# interface.net
KiCad netlist of a schematic drawn in EAGLE
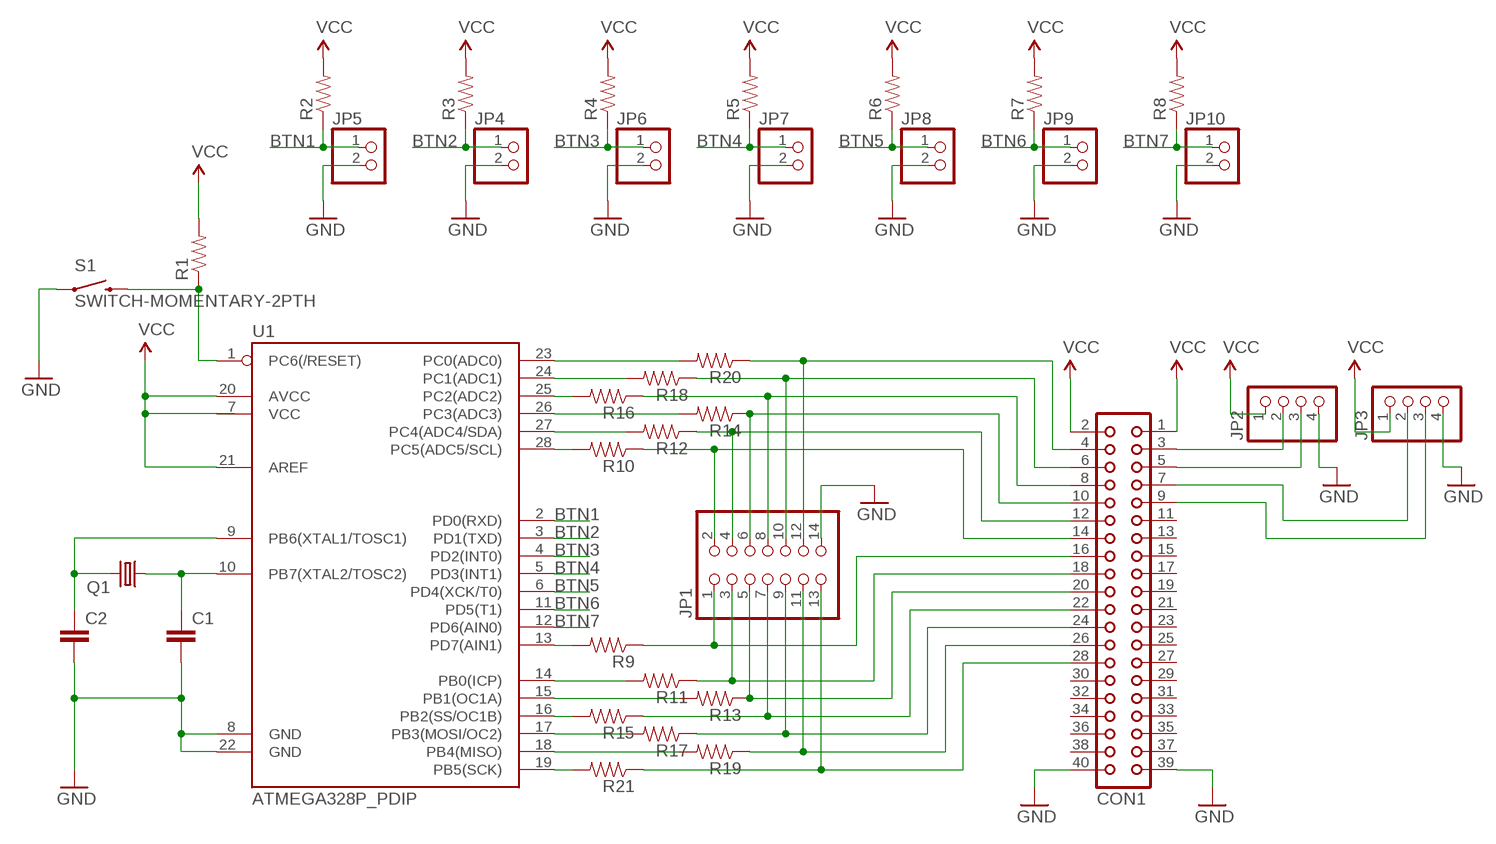
[diagram p0: schematic, sheet 1]

(export (version "E")
  (design (tool "Eeschema 10.0.6"))
  (components
    (comp (ref "C1")
      (value "CAPPTH")
      (footprint "eagle-import:CAP-PTH-SMALL")
      (libsource (lib "eagle-import") (part "CAPPTH"))
    )
    (comp (ref "C2")
      (value "CAPPTH")
      (footprint "eagle-import:CAP-PTH-SMALL")
      (libsource (lib "eagle-import") (part "CAPPTH"))
    )
    (comp (ref "CON1")
      (value "CON40")
      (footprint "eagle-import:CON40")
      (libsource (lib "eagle-import") (part "CON40"))
    )
    (comp (ref "JP1")
      (value "PINHD-2X7")
      (footprint "eagle-import:2X07")
      (libsource (lib "eagle-import") (part "PINHD-2X7"))
    )
    (comp (ref "JP2")
      (value "PINHD-1X4")
      (footprint "eagle-import:1X04")
      (libsource (lib "eagle-import") (part "PINHD-1X4"))
    )
    (comp (ref "JP3")
      (value "PINHD-1X4")
      (footprint "eagle-import:1X04")
      (libsource (lib "eagle-import") (part "PINHD-1X4"))
    )
    (comp (ref "JP4")
      (value "PINHD-1X2")
      (footprint "eagle-import:1X02")
      (libsource (lib "eagle-import") (part "PINHD-1X2"))
    )
    (comp (ref "JP5")
      (value "PINHD-1X2")
      (footprint "eagle-import:1X02")
      (libsource (lib "eagle-import") (part "PINHD-1X2"))
    )
    (comp (ref "JP6")
      (value "PINHD-1X2")
      (footprint "eagle-import:1X02")
      (libsource (lib "eagle-import") (part "PINHD-1X2"))
    )
    (comp (ref "JP7")
      (value "PINHD-1X2")
      (footprint "eagle-import:1X02")
      (libsource (lib "eagle-import") (part "PINHD-1X2"))
    )
    (comp (ref "JP8")
      (value "PINHD-1X2")
      (footprint "eagle-import:1X02")
      (libsource (lib "eagle-import") (part "PINHD-1X2"))
    )
    (comp (ref "JP9")
      (value "PINHD-1X2")
      (footprint "eagle-import:1X02")
      (libsource (lib "eagle-import") (part "PINHD-1X2"))
    )
    (comp (ref "JP10")
      (value "PINHD-1X2")
      (footprint "eagle-import:1X02")
      (libsource (lib "eagle-import") (part "PINHD-1X2"))
    )
    (comp (ref "Q1")
      (value "CRYSTALHC49S")
      (footprint "eagle-import:HC49_S")
      (libsource (lib "eagle-import") (part "CRYSTALHC49S"))
    )
    (comp (ref "R1")
      (value "RESISTORPTH-1/4W")
      (footprint "eagle-import:AXIAL-0.4")
      (libsource (lib "eagle-import") (part "RESISTORPTH-1/4W"))
    )
    (comp (ref "R2")
      (value "RESISTORPTH-1/4W")
      (footprint "eagle-import:AXIAL-0.4")
      (libsource (lib "eagle-import") (part "RESISTORPTH-1/4W"))
    )
    (comp (ref "R3")
      (value "RESISTORPTH-1/4W")
      (footprint "eagle-import:AXIAL-0.4")
      (libsource (lib "eagle-import") (part "RESISTORPTH-1/4W"))
    )
    (comp (ref "R4")
      (value "RESISTORPTH-1/4W")
      (footprint "eagle-import:AXIAL-0.4")
      (libsource (lib "eagle-import") (part "RESISTORPTH-1/4W"))
    )
    (comp (ref "R5")
      (value "RESISTORPTH-1/4W")
      (footprint "eagle-import:AXIAL-0.4")
      (libsource (lib "eagle-import") (part "RESISTORPTH-1/4W"))
    )
    (comp (ref "R6")
      (value "RESISTORPTH-1/4W")
      (footprint "eagle-import:AXIAL-0.4")
      (libsource (lib "eagle-import") (part "RESISTORPTH-1/4W"))
    )
    (comp (ref "R7")
      (value "RESISTORPTH-1/4W")
      (footprint "eagle-import:AXIAL-0.4")
      (libsource (lib "eagle-import") (part "RESISTORPTH-1/4W"))
    )
    (comp (ref "R8")
      (value "RESISTORPTH-1/4W")
      (footprint "eagle-import:AXIAL-0.4")
      (libsource (lib "eagle-import") (part "RESISTORPTH-1/4W"))
    )
    (comp (ref "R9")
      (value "RESISTORPTH-1/4W")
      (footprint "eagle-import:AXIAL-0.4")
      (libsource (lib "eagle-import") (part "RESISTORPTH-1/4W"))
    )
    (comp (ref "R10")
      (value "RESISTORPTH-1/4W")
      (footprint "eagle-import:AXIAL-0.4")
      (libsource (lib "eagle-import") (part "RESISTORPTH-1/4W"))
    )
    (comp (ref "R11")
      (value "RESISTORPTH-1/4W")
      (footprint "eagle-import:AXIAL-0.4")
      (libsource (lib "eagle-import") (part "RESISTORPTH-1/4W"))
    )
    (comp (ref "R12")
      (value "RESISTORPTH-1/4W")
      (footprint "eagle-import:AXIAL-0.4")
      (libsource (lib "eagle-import") (part "RESISTORPTH-1/4W"))
    )
    (comp (ref "R13")
      (value "RESISTORPTH-1/4W")
      (footprint "eagle-import:AXIAL-0.4")
      (libsource (lib "eagle-import") (part "RESISTORPTH-1/4W"))
    )
    (comp (ref "R14")
      (value "RESISTORPTH-1/4W")
      (footprint "eagle-import:AXIAL-0.4")
      (libsource (lib "eagle-import") (part "RESISTORPTH-1/4W"))
    )
    (comp (ref "R15")
      (value "RESISTORPTH-1/4W")
      (footprint "eagle-import:AXIAL-0.4")
      (libsource (lib "eagle-import") (part "RESISTORPTH-1/4W"))
    )
    (comp (ref "R16")
      (value "RESISTORPTH-1/4W")
      (footprint "eagle-import:AXIAL-0.4")
      (libsource (lib "eagle-import") (part "RESISTORPTH-1/4W"))
    )
    (comp (ref "R17")
      (value "RESISTORPTH-1/4W")
      (footprint "eagle-import:AXIAL-0.4")
      (libsource (lib "eagle-import") (part "RESISTORPTH-1/4W"))
    )
    (comp (ref "R18")
      (value "RESISTORPTH-1/4W")
      (footprint "eagle-import:AXIAL-0.4")
      (libsource (lib "eagle-import") (part "RESISTORPTH-1/4W"))
    )
    (comp (ref "R19")
      (value "RESISTORPTH-1/4W")
      (footprint "eagle-import:AXIAL-0.4")
      (libsource (lib "eagle-import") (part "RESISTORPTH-1/4W"))
    )
    (comp (ref "R20")
      (value "RESISTORPTH-1/4W")
      (footprint "eagle-import:AXIAL-0.4")
      (libsource (lib "eagle-import") (part "RESISTORPTH-1/4W"))
    )
    (comp (ref "R21")
      (value "RESISTORPTH-1/4W")
      (footprint "eagle-import:AXIAL-0.4")
      (libsource (lib "eagle-import") (part "RESISTORPTH-1/4W"))
    )
    (comp (ref "S1")
      (value "SWITCH-MOMENTARY-2PTH")
      (footprint "eagle-import:TACTILE-PTH")
      (libsource (lib "eagle-import") (part "SWITCH-MOMENTARY-2PTH"))
    )
    (comp (ref "U1")
      (value "ATMEGA328P_PDIP")
      (footprint "eagle-import:DIL28-3")
      (libsource (lib "eagle-import") (part "ATMEGA328P_PDIP"))
    )
  )
  (nets
    (net (code "1") (name "/BTN1") (class "Default")
      (node (ref "JP5") (pin "1") (pinfunction "1_1") (pintype "passive"))
      (node (ref "R2") (pin "P$1") (pinfunction "1_P$1") (pintype "passive"))
      (node (ref "U1") (pin "2") (pinfunction "PD0(RXD)_2") (pintype "bidirectional"))
    )
    (net (code "2") (name "/BTN2") (class "Default")
      (node (ref "JP4") (pin "1") (pinfunction "1_1") (pintype "passive"))
      (node (ref "R3") (pin "P$1") (pinfunction "1_P$1") (pintype "passive"))
      (node (ref "U1") (pin "3") (pinfunction "PD1(TXD)_3") (pintype "bidirectional"))
    )
    (net (code "3") (name "/BTN3") (class "Default")
      (node (ref "JP6") (pin "1") (pinfunction "1_1") (pintype "passive"))
      (node (ref "R4") (pin "P$1") (pinfunction "1_P$1") (pintype "passive"))
      (node (ref "U1") (pin "4") (pinfunction "PD2(INT0)_4") (pintype "bidirectional"))
    )
    (net (code "4") (name "/BTN4") (class "Default")
      (node (ref "JP7") (pin "1") (pinfunction "1_1") (pintype "passive"))
      (node (ref "R5") (pin "P$1") (pinfunction "1_P$1") (pintype "passive"))
      (node (ref "U1") (pin "5") (pinfunction "PD3(INT1)_5") (pintype "bidirectional"))
    )
    (net (code "5") (name "/BTN5") (class "Default")
      (node (ref "JP8") (pin "1") (pinfunction "1_1") (pintype "passive"))
      (node (ref "R6") (pin "P$1") (pinfunction "1_P$1") (pintype "passive"))
      (node (ref "U1") (pin "6") (pinfunction "PD4(XCK/T0)_6") (pintype "bidirectional"))
    )
    (net (code "6") (name "/BTN6") (class "Default")
      (node (ref "JP9") (pin "1") (pinfunction "1_1") (pintype "passive"))
      (node (ref "R7") (pin "P$1") (pinfunction "1_P$1") (pintype "passive"))
      (node (ref "U1") (pin "11") (pinfunction "PD5(T1)_11") (pintype "bidirectional"))
    )
    (net (code "7") (name "/BTN7") (class "Default")
      (node (ref "JP10") (pin "1") (pinfunction "1_1") (pintype "passive"))
      (node (ref "R8") (pin "P$1") (pinfunction "1_P$1") (pintype "passive"))
      (node (ref "U1") (pin "12") (pinfunction "PD6(AIN0)_12") (pintype "bidirectional"))
    )
    (net (code "8") (name "GND") (class "Default")
      (node (ref "C1") (pin "2") (pinfunction "2_2") (pintype "passive"))
      (node (ref "C2") (pin "2") (pinfunction "2_2") (pintype "passive"))
      (node (ref "CON1") (pin "39") (pinfunction "39_39") (pintype "passive"))
      (node (ref "CON1") (pin "40") (pinfunction "40_40") (pintype "passive"))
      (node (ref "JP1") (pin "14") (pinfunction "14_14") (pintype "passive"))
      (node (ref "JP10") (pin "2") (pinfunction "2_2") (pintype "passive"))
      (node (ref "JP2") (pin "4") (pinfunction "4_4") (pintype "passive"))
      (node (ref "JP3") (pin "4") (pinfunction "4_4") (pintype "passive"))
      (node (ref "JP4") (pin "2") (pinfunction "2_2") (pintype "passive"))
      (node (ref "JP5") (pin "2") (pinfunction "2_2") (pintype "passive"))
      (node (ref "JP6") (pin "2") (pinfunction "2_2") (pintype "passive"))
      (node (ref "JP7") (pin "2") (pinfunction "2_2") (pintype "passive"))
      (node (ref "JP8") (pin "2") (pinfunction "2_2") (pintype "passive"))
      (node (ref "JP9") (pin "2") (pinfunction "2_2") (pintype "passive"))
      (node (ref "S1") (pin "1") (pinfunction "1_1") (pintype "passive"))
      (node (ref "U1") (pin "22") (pinfunction "GND_22") (pintype "bidirectional"))
      (node (ref "U1") (pin "8") (pinfunction "GND_8") (pintype "bidirectional"))
    )
    (net (code "9") (name "Net-(CON1-Pad3)") (class "Default")
      (node (ref "CON1") (pin "3") (pinfunction "3_3") (pintype "passive"))
      (node (ref "JP2") (pin "2") (pinfunction "2_2") (pintype "passive"))
    )
    (net (code "10") (name "Net-(CON1-Pad5)") (class "Default")
      (node (ref "CON1") (pin "5") (pinfunction "5_5") (pintype "passive"))
      (node (ref "JP2") (pin "3") (pinfunction "3_3") (pintype "passive"))
    )
    (net (code "11") (name "Net-(CON1-Pad7)") (class "Default")
      (node (ref "CON1") (pin "7") (pinfunction "7_7") (pintype "passive"))
      (node (ref "JP3") (pin "2") (pinfunction "2_2") (pintype "passive"))
    )
    (net (code "12") (name "Net-(CON1-Pad9)") (class "Default")
      (node (ref "CON1") (pin "9") (pinfunction "9_9") (pintype "passive"))
      (node (ref "JP3") (pin "3") (pinfunction "3_3") (pintype "passive"))
    )
    (net (code "13") (name "Net-(R1-1)") (class "Default")
      (node (ref "R1") (pin "P$1") (pinfunction "1_P$1") (pintype "passive"))
      (node (ref "S1") (pin "3") (pinfunction "2_3") (pintype "passive"))
      (node (ref "U1") (pin "1") (pinfunction "PC6(/RESET)_1") (pintype "bidirectional"))
    )
    (net (code "14") (name "Net-(R9-1)") (class "Default")
      (node (ref "CON1") (pin "16") (pinfunction "16_16") (pintype "passive"))
      (node (ref "JP1") (pin "1") (pinfunction "1_1") (pintype "passive"))
      (node (ref "R9") (pin "P$1") (pinfunction "1_P$1") (pintype "passive"))
    )
    (net (code "15") (name "Net-(R9-2)") (class "Default")
      (node (ref "R9") (pin "P$2") (pinfunction "2_P$2") (pintype "passive"))
      (node (ref "U1") (pin "13") (pinfunction "PD7(AIN1)_13") (pintype "bidirectional"))
    )
    (net (code "16") (name "Net-(R10-1)") (class "Default")
      (node (ref "CON1") (pin "14") (pinfunction "14_14") (pintype "passive"))
      (node (ref "JP1") (pin "2") (pinfunction "2_2") (pintype "passive"))
      (node (ref "R10") (pin "P$1") (pinfunction "1_P$1") (pintype "passive"))
    )
    (net (code "17") (name "Net-(R10-2)") (class "Default")
      (node (ref "R10") (pin "P$2") (pinfunction "2_P$2") (pintype "passive"))
      (node (ref "U1") (pin "28") (pinfunction "PC5(ADC5/SCL)_28") (pintype "bidirectional"))
    )
    (net (code "18") (name "Net-(R11-1)") (class "Default")
      (node (ref "CON1") (pin "18") (pinfunction "18_18") (pintype "passive"))
      (node (ref "JP1") (pin "3") (pinfunction "3_3") (pintype "passive"))
      (node (ref "R11") (pin "P$1") (pinfunction "1_P$1") (pintype "passive"))
    )
    (net (code "19") (name "Net-(R11-2)") (class "Default")
      (node (ref "R11") (pin "P$2") (pinfunction "2_P$2") (pintype "passive"))
      (node (ref "U1") (pin "14") (pinfunction "PB0(ICP)_14") (pintype "bidirectional"))
    )
    (net (code "20") (name "Net-(R12-1)") (class "Default")
      (node (ref "CON1") (pin "12") (pinfunction "12_12") (pintype "passive"))
      (node (ref "JP1") (pin "4") (pinfunction "4_4") (pintype "passive"))
      (node (ref "R12") (pin "P$1") (pinfunction "1_P$1") (pintype "passive"))
    )
    (net (code "21") (name "Net-(R12-2)") (class "Default")
      (node (ref "R12") (pin "P$2") (pinfunction "2_P$2") (pintype "passive"))
      (node (ref "U1") (pin "27") (pinfunction "PC4(ADC4/SDA)_27") (pintype "bidirectional"))
    )
    (net (code "22") (name "Net-(R13-1)") (class "Default")
      (node (ref "CON1") (pin "20") (pinfunction "20_20") (pintype "passive"))
      (node (ref "JP1") (pin "5") (pinfunction "5_5") (pintype "passive"))
      (node (ref "R13") (pin "P$1") (pinfunction "1_P$1") (pintype "passive"))
    )
    (net (code "23") (name "Net-(R13-2)") (class "Default")
      (node (ref "R13") (pin "P$2") (pinfunction "2_P$2") (pintype "passive"))
      (node (ref "U1") (pin "15") (pinfunction "PB1(OC1A)_15") (pintype "bidirectional"))
    )
    (net (code "24") (name "Net-(R14-1)") (class "Default")
      (node (ref "CON1") (pin "10") (pinfunction "10_10") (pintype "passive"))
      (node (ref "JP1") (pin "6") (pinfunction "6_6") (pintype "passive"))
      (node (ref "R14") (pin "P$1") (pinfunction "1_P$1") (pintype "passive"))
    )
    (net (code "25") (name "Net-(R14-2)") (class "Default")
      (node (ref "R14") (pin "P$2") (pinfunction "2_P$2") (pintype "passive"))
      (node (ref "U1") (pin "26") (pinfunction "PC3(ADC3)_26") (pintype "bidirectional"))
    )
    (net (code "26") (name "Net-(R15-1)") (class "Default")
      (node (ref "CON1") (pin "22") (pinfunction "22_22") (pintype "passive"))
      (node (ref "JP1") (pin "7") (pinfunction "7_7") (pintype "passive"))
      (node (ref "R15") (pin "P$1") (pinfunction "1_P$1") (pintype "passive"))
    )
    (net (code "27") (name "Net-(R15-2)") (class "Default")
      (node (ref "R15") (pin "P$2") (pinfunction "2_P$2") (pintype "passive"))
      (node (ref "U1") (pin "16") (pinfunction "PB2(SS/OC1B)_16") (pintype "bidirectional"))
    )
    (net (code "28") (name "Net-(R16-1)") (class "Default")
      (node (ref "CON1") (pin "8") (pinfunction "8_8") (pintype "passive"))
      (node (ref "JP1") (pin "8") (pinfunction "8_8") (pintype "passive"))
      (node (ref "R16") (pin "P$1") (pinfunction "1_P$1") (pintype "passive"))
    )
    (net (code "29") (name "Net-(R16-2)") (class "Default")
      (node (ref "R16") (pin "P$2") (pinfunction "2_P$2") (pintype "passive"))
      (node (ref "U1") (pin "25") (pinfunction "PC2(ADC2)_25") (pintype "bidirectional"))
    )
    (net (code "30") (name "Net-(R17-1)") (class "Default")
      (node (ref "CON1") (pin "24") (pinfunction "24_24") (pintype "passive"))
      (node (ref "JP1") (pin "9") (pinfunction "9_9") (pintype "passive"))
      (node (ref "R17") (pin "P$1") (pinfunction "1_P$1") (pintype "passive"))
    )
    (net (code "31") (name "Net-(R17-2)") (class "Default")
      (node (ref "R17") (pin "P$2") (pinfunction "2_P$2") (pintype "passive"))
      (node (ref "U1") (pin "17") (pinfunction "PB3(MOSI/OC2)_17") (pintype "bidirectional"))
    )
    (net (code "32") (name "Net-(R18-1)") (class "Default")
      (node (ref "CON1") (pin "6") (pinfunction "6_6") (pintype "passive"))
      (node (ref "JP1") (pin "10") (pinfunction "10_10") (pintype "passive"))
      (node (ref "R18") (pin "P$1") (pinfunction "1_P$1") (pintype "passive"))
    )
    (net (code "33") (name "Net-(R18-2)") (class "Default")
      (node (ref "R18") (pin "P$2") (pinfunction "2_P$2") (pintype "passive"))
      (node (ref "U1") (pin "24") (pinfunction "PC1(ADC1)_24") (pintype "bidirectional"))
    )
    (net (code "34") (name "Net-(R19-1)") (class "Default")
      (node (ref "CON1") (pin "26") (pinfunction "26_26") (pintype "passive"))
      (node (ref "JP1") (pin "11") (pinfunction "11_11") (pintype "passive"))
      (node (ref "R19") (pin "P$1") (pinfunction "1_P$1") (pintype "passive"))
    )
    (net (code "35") (name "Net-(R19-2)") (class "Default")
      (node (ref "R19") (pin "P$2") (pinfunction "2_P$2") (pintype "passive"))
      (node (ref "U1") (pin "18") (pinfunction "PB4(MISO)_18") (pintype "bidirectional"))
    )
    (net (code "36") (name "Net-(R20-1)") (class "Default")
      (node (ref "CON1") (pin "4") (pinfunction "4_4") (pintype "passive"))
      (node (ref "JP1") (pin "12") (pinfunction "12_12") (pintype "passive"))
      (node (ref "R20") (pin "P$1") (pinfunction "1_P$1") (pintype "passive"))
    )
    (net (code "37") (name "Net-(R20-2)") (class "Default")
      (node (ref "R20") (pin "P$2") (pinfunction "2_P$2") (pintype "passive"))
      (node (ref "U1") (pin "23") (pinfunction "PC0(ADC0)_23") (pintype "bidirectional"))
    )
    (net (code "38") (name "Net-(R21-1)") (class "Default")
      (node (ref "CON1") (pin "28") (pinfunction "28_28") (pintype "passive"))
      (node (ref "JP1") (pin "13") (pinfunction "13_13") (pintype "passive"))
      (node (ref "R21") (pin "P$1") (pinfunction "1_P$1") (pintype "passive"))
    )
    (net (code "39") (name "Net-(R21-2)") (class "Default")
      (node (ref "R21") (pin "P$2") (pinfunction "2_P$2") (pintype "passive"))
      (node (ref "U1") (pin "19") (pinfunction "PB5(SCK)_19") (pintype "bidirectional"))
    )
    (net (code "40") (name "Net-(U1-PB6(XTAL1{slash}TOSC1))") (class "Default")
      (node (ref "C2") (pin "1") (pinfunction "1_1") (pintype "passive"))
      (node (ref "Q1") (pin "2") (pinfunction "2_2") (pintype "passive"))
      (node (ref "U1") (pin "9") (pinfunction "PB6(XTAL1/TOSC1)_9") (pintype "bidirectional"))
    )
    (net (code "41") (name "Net-(U1-PB7(XTAL2{slash}TOSC2))") (class "Default")
      (node (ref "C1") (pin "1") (pinfunction "1_1") (pintype "passive"))
      (node (ref "Q1") (pin "1") (pinfunction "1_1") (pintype "passive"))
      (node (ref "U1") (pin "10") (pinfunction "PB7(XTAL2/TOSC2)_10") (pintype "bidirectional"))
    )
    (net (code "42") (name "VCC") (class "Default")
      (node (ref "CON1") (pin "1") (pinfunction "1_1") (pintype "passive"))
      (node (ref "CON1") (pin "2") (pinfunction "2_2") (pintype "passive"))
      (node (ref "JP2") (pin "1") (pinfunction "1_1") (pintype "passive"))
      (node (ref "JP3") (pin "1") (pinfunction "1_1") (pintype "passive"))
      (node (ref "R1") (pin "P$2") (pinfunction "2_P$2") (pintype "passive"))
      (node (ref "R2") (pin "P$2") (pinfunction "2_P$2") (pintype "passive"))
      (node (ref "R3") (pin "P$2") (pinfunction "2_P$2") (pintype "passive"))
      (node (ref "R4") (pin "P$2") (pinfunction "2_P$2") (pintype "passive"))
      (node (ref "R5") (pin "P$2") (pinfunction "2_P$2") (pintype "passive"))
      (node (ref "R6") (pin "P$2") (pinfunction "2_P$2") (pintype "passive"))
      (node (ref "R7") (pin "P$2") (pinfunction "2_P$2") (pintype "passive"))
      (node (ref "R8") (pin "P$2") (pinfunction "2_P$2") (pintype "passive"))
      (node (ref "U1") (pin "20") (pinfunction "AVCC_20") (pintype "bidirectional"))
      (node (ref "U1") (pin "21") (pinfunction "AREF_21") (pintype "bidirectional"))
    )
    (net (code "43") (name "unconnected-(CON1-Pad11)") (class "Default")
      (node (ref "CON1") (pin "11") (pinfunction "11_11") (pintype "passive"))
    )
    (net (code "44") (name "unconnected-(CON1-Pad13)") (class "Default")
      (node (ref "CON1") (pin "13") (pinfunction "13_13") (pintype "passive"))
    )
    (net (code "45") (name "unconnected-(CON1-Pad15)") (class "Default")
      (node (ref "CON1") (pin "15") (pinfunction "15_15") (pintype "passive"))
    )
    (net (code "46") (name "unconnected-(CON1-Pad17)") (class "Default")
      (node (ref "CON1") (pin "17") (pinfunction "17_17") (pintype "passive"))
    )
    (net (code "47") (name "unconnected-(CON1-Pad19)") (class "Default")
      (node (ref "CON1") (pin "19") (pinfunction "19_19") (pintype "passive"))
    )
    (net (code "48") (name "unconnected-(CON1-Pad21)") (class "Default")
      (node (ref "CON1") (pin "21") (pinfunction "21_21") (pintype "passive"))
    )
    (net (code "49") (name "unconnected-(CON1-Pad23)") (class "Default")
      (node (ref "CON1") (pin "23") (pinfunction "23_23") (pintype "passive"))
    )
    (net (code "50") (name "unconnected-(CON1-Pad25)") (class "Default")
      (node (ref "CON1") (pin "25") (pinfunction "25_25") (pintype "passive"))
    )
    (net (code "51") (name "unconnected-(CON1-Pad27)") (class "Default")
      (node (ref "CON1") (pin "27") (pinfunction "27_27") (pintype "passive"))
    )
    (net (code "52") (name "unconnected-(CON1-Pad29)") (class "Default")
      (node (ref "CON1") (pin "29") (pinfunction "29_29") (pintype "passive"))
    )
    (net (code "53") (name "unconnected-(CON1-Pad30)") (class "Default")
      (node (ref "CON1") (pin "30") (pinfunction "30_30") (pintype "passive"))
    )
    (net (code "54") (name "unconnected-(CON1-Pad31)") (class "Default")
      (node (ref "CON1") (pin "31") (pinfunction "31_31") (pintype "passive"))
    )
    (net (code "55") (name "unconnected-(CON1-Pad32)") (class "Default")
      (node (ref "CON1") (pin "32") (pinfunction "32_32") (pintype "passive"))
    )
    (net (code "56") (name "unconnected-(CON1-Pad33)") (class "Default")
      (node (ref "CON1") (pin "33") (pinfunction "33_33") (pintype "passive"))
    )
    (net (code "57") (name "unconnected-(CON1-Pad34)") (class "Default")
      (node (ref "CON1") (pin "34") (pinfunction "34_34") (pintype "passive"))
    )
    (net (code "58") (name "unconnected-(CON1-Pad35)") (class "Default")
      (node (ref "CON1") (pin "35") (pinfunction "35_35") (pintype "passive"))
    )
    (net (code "59") (name "unconnected-(CON1-Pad36)") (class "Default")
      (node (ref "CON1") (pin "36") (pinfunction "36_36") (pintype "passive"))
    )
    (net (code "60") (name "unconnected-(CON1-Pad37)") (class "Default")
      (node (ref "CON1") (pin "37") (pinfunction "37_37") (pintype "passive"))
    )
    (net (code "61") (name "unconnected-(CON1-Pad38)") (class "Default")
      (node (ref "CON1") (pin "38") (pinfunction "38_38") (pintype "passive"))
    )
    (net (code "62") (name "unconnected-(U1-VCC-Pad7)") (class "Default")
      (node (ref "U1") (pin "7") (pinfunction "VCC_7") (pintype "bidirectional"))
    )
  )
)
